# AnalogOut.net
KiCad netlist of a schematic drawn in Altium Designer
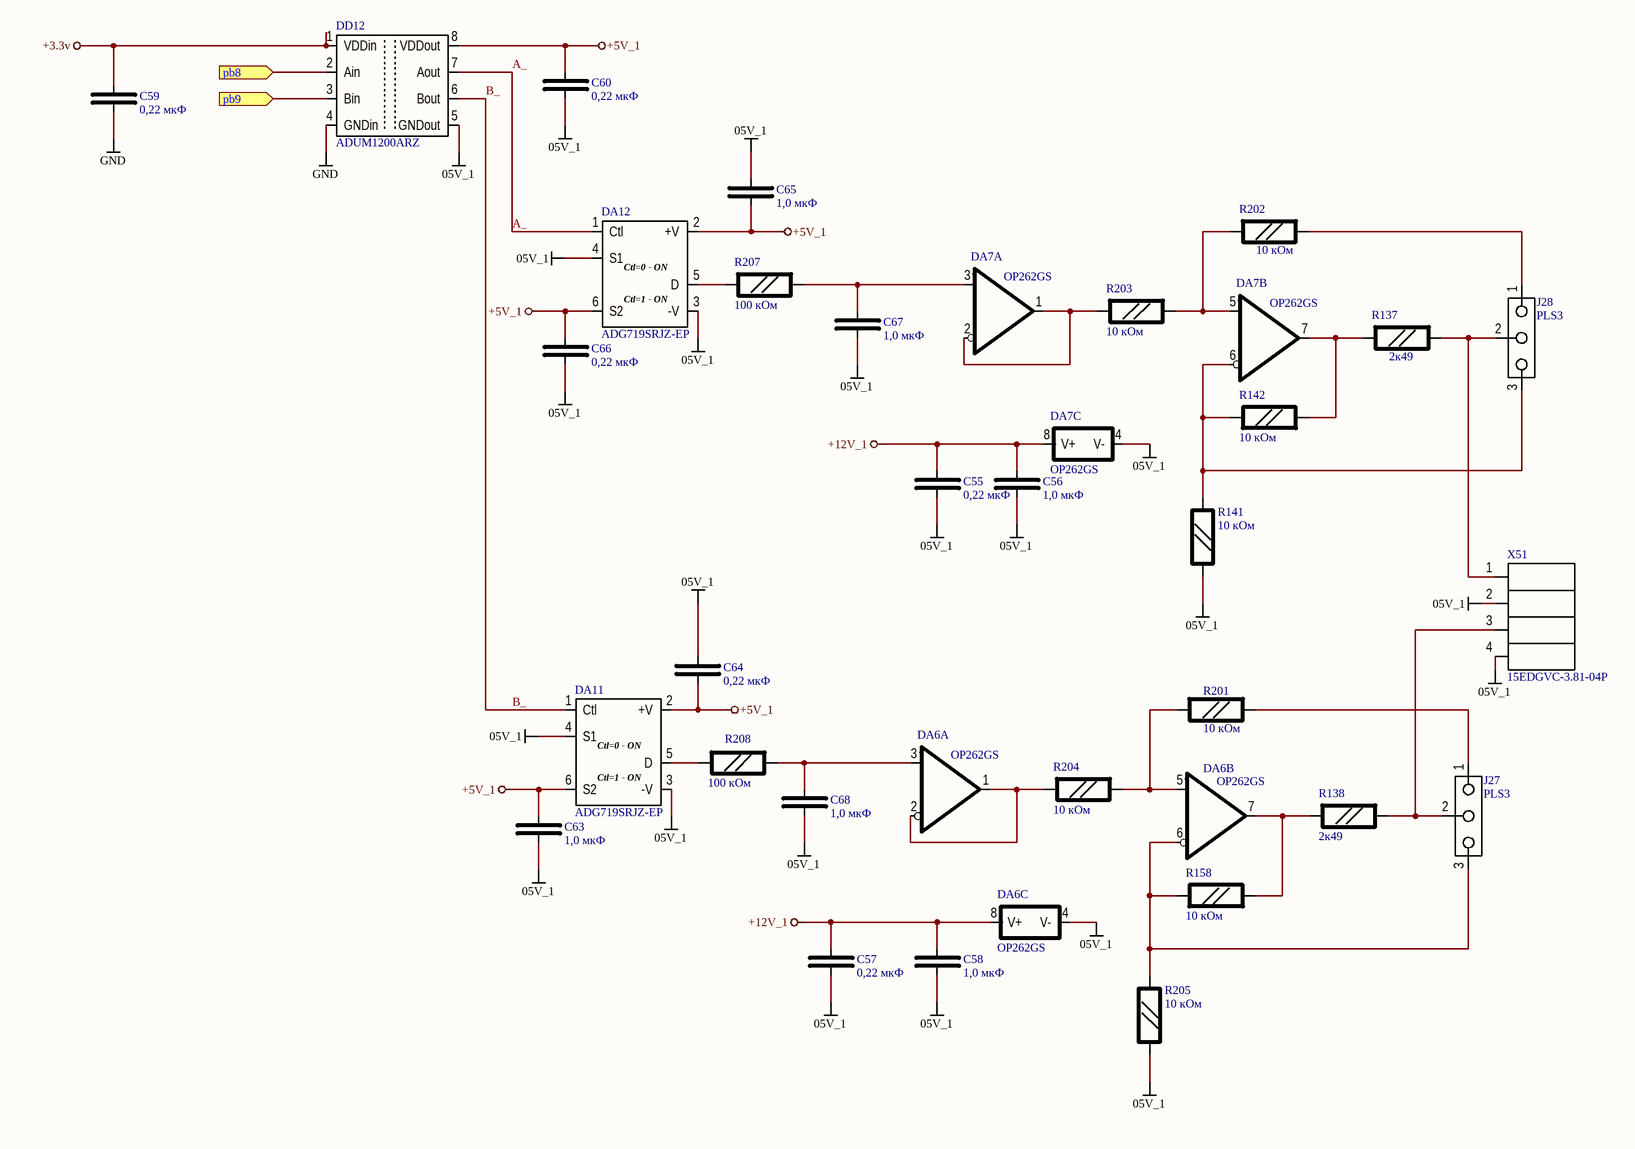
[diagram p0: AnalogOut.SchDoc]

(export (version "E")
  (design (tool "Eeschema 10.0.6"))
  (components
    (comp (ref "C55")
      (value "0,22 мкФ")
      (footprint "SMD0805CAP")
      (description "Чип конденсатор 0805")
      (fields (field (name "VOLTAGE") "50V"))
      (libsource (lib "SL02_22F") (part "C0805"))
    )
    (comp (ref "C56")
      (value "1,0 мкФ")
      (footprint "SMD0805CAP")
      (description "Чип конденсатор 0805")
      (fields (field (name "VOLTAGE") "50V"))
      (libsource (lib "SL02_22F") (part "C0805"))
    )
    (comp (ref "C57")
      (value "0,22 мкФ")
      (footprint "SMD0805CAP")
      (description "Чип конденсатор 0805")
      (fields (field (name "VOLTAGE") "50V"))
      (libsource (lib "SL02_22F") (part "C0805"))
    )
    (comp (ref "C58")
      (value "1,0 мкФ")
      (footprint "SMD0805CAP")
      (description "Чип конденсатор 0805")
      (fields (field (name "VOLTAGE") "50V"))
      (libsource (lib "SL02_22F") (part "C0805"))
    )
    (comp (ref "C59")
      (value "0,22 мкФ")
      (footprint "SMD0805CAP")
      (description "Чип конденсатор 0805")
      (fields (field (name "VOLTAGE") "50V"))
      (libsource (lib "SL02_22F") (part "C0805"))
    )
    (comp (ref "C60")
      (value "0,22 мкФ")
      (footprint "SMD0805CAP")
      (description "Чип конденсатор 0805")
      (fields (field (name "VOLTAGE") "50V"))
      (libsource (lib "SL02_22F") (part "C0805"))
    )
    (comp (ref "C63")
      (value "1,0 мкФ")
      (footprint "SMD0805CAP")
      (description "Чип конденсатор 0805")
      (fields (field (name "VOLTAGE") "50V"))
      (libsource (lib "SL02_22F") (part "C0805"))
    )
    (comp (ref "C64")
      (value "0,22 мкФ")
      (footprint "SMD0805CAP")
      (description "Чип конденсатор 0805")
      (fields (field (name "VOLTAGE") "50V"))
      (libsource (lib "SL02_22F") (part "C0805"))
    )
    (comp (ref "C65")
      (value "1,0 мкФ")
      (footprint "SMD0805CAP")
      (description "Чип конденсатор 0805")
      (fields (field (name "VOLTAGE") "50V"))
      (libsource (lib "SL02_22F") (part "C0805"))
    )
    (comp (ref "C66")
      (value "0,22 мкФ")
      (footprint "SMD0805CAP")
      (description "Чип конденсатор 0805")
      (fields (field (name "VOLTAGE") "50V"))
      (libsource (lib "SL02_22F") (part "C0805"))
    )
    (comp (ref "C67")
      (value "1,0 мкФ")
      (footprint "SMD0805CAP")
      (description "Чип конденсатор 0805")
      (fields (field (name "VOLTAGE") "50V"))
      (libsource (lib "SL02_22F") (part "C0805"))
    )
    (comp (ref "C68")
      (value "1,0 мкФ")
      (footprint "SMD0805CAP")
      (description "Чип конденсатор 0805")
      (fields (field (name "VOLTAGE") "50V"))
      (libsource (lib "SL02_22F") (part "C0805"))
    )
    (comp (ref "DA6")
      (value "OP262GS")
      (footprint "SO8")
      (description "ОУ сдвоенный R2R out")
      (fields (field (name "VOLTAGE") "2.7..12V"))
      (libsource (lib "SL02_22F") (part "OP262GS"))
    )
    (comp (ref "DA7")
      (value "OP262GS")
      (footprint "SO8")
      (description "ОУ сдвоенный R2R out")
      (fields (field (name "VOLTAGE") "2.7..12V"))
      (libsource (lib "SL02_22F") (part "OP262GS"))
    )
    (comp (ref "DA11")
      (value "ADG719SRJZ-EP")
      (footprint "SOT23-6")
      (description "аналоговый ключ SPDT")
      (fields (field (name "VOLTAGE") "1V8.. 5V5"))
      (libsource (lib "L02_22F") (part "ADG719BRJ"))
    )
    (comp (ref "DA12")
      (value "ADG719SRJZ-EP")
      (footprint "SOT23-6")
      (description "аналоговый ключ SPDT")
      (fields (field (name "VOLTAGE") "1V8.. 5V5"))
      (libsource (lib "L02_22F") (part "ADG719BRJ"))
    )
    (comp (ref "DD12")
      (value "ADUM1200ARZ")
      (footprint "SO8")
      (description "2х канальный цифровой изолятор")
      (fields (field (name "VOLTAGE") "3..5V"))
      (libsource (lib "L02_22F") (part "ADUM1200ARZ"))
    )
    (comp (ref "J27")
      (value "PLS3")
      (footprint "HDR1X3")
      (description "Джампер PLS3 2.54мм")
      (libsource (lib "L02_22F") (part "PLS3"))
    )
    (comp (ref "J28")
      (value "PLS3")
      (footprint "HDR1X3")
      (description "Джампер PLS3 2.54мм")
      (libsource (lib "L02_22F") (part "PLS3"))
    )
    (comp (ref "R137")
      (value "2к49")
      (footprint "SMD0805RES")
      (description "Чип резистор 0805")
      (fields (field (name "TOLERANCE") "1%"))
      (libsource (lib "SL02_22F") (part "R0805"))
    )
    (comp (ref "R138")
      (value "2к49")
      (footprint "SMD0805RES")
      (description "Чип резистор 0805")
      (fields (field (name "TOLERANCE") "1%"))
      (libsource (lib "SL02_22F") (part "R0805"))
    )
    (comp (ref "R141")
      (value "10 кОм")
      (footprint "SMD0805RES")
      (description "Чип резистор 0805")
      (fields (field (name "TOLERANCE") "1%"))
      (libsource (lib "SL02_22F") (part "R0805"))
    )
    (comp (ref "R142")
      (value "10 кОм")
      (footprint "SMD0805RES")
      (description "Чип резистор 0805")
      (fields (field (name "TOLERANCE") "1%"))
      (libsource (lib "SL02_22F") (part "R0805"))
    )
    (comp (ref "R158")
      (value "10 кОм")
      (footprint "SMD0805RES")
      (description "Чип резистор 0805")
      (fields (field (name "TOLERANCE") "1%"))
      (libsource (lib "SL02_22F") (part "R0805"))
    )
    (comp (ref "R201")
      (value "10 кОм")
      (footprint "SMD0805RES")
      (description "Чип резистор 0805")
      (fields (field (name "TOLERANCE") "1%"))
      (libsource (lib "SL02_22F") (part "R0805"))
    )
    (comp (ref "R202")
      (value "10 кОм")
      (footprint "SMD0805RES")
      (description "Чип резистор 0805")
      (fields (field (name "TOLERANCE") "1%"))
      (libsource (lib "SL02_22F") (part "R0805"))
    )
    (comp (ref "R203")
      (value "10 кОм")
      (footprint "SMD0805RES")
      (description "Чип резистор 0805")
      (fields (field (name "TOLERANCE") "1%"))
      (libsource (lib "SL02_22F") (part "R0805"))
    )
    (comp (ref "R204")
      (value "10 кОм")
      (footprint "SMD0805RES")
      (description "Чип резистор 0805")
      (fields (field (name "TOLERANCE") "1%"))
      (libsource (lib "SL02_22F") (part "R0805"))
    )
    (comp (ref "R205")
      (value "10 кОм")
      (footprint "SMD0805RES")
      (description "Чип резистор 0805")
      (fields (field (name "TOLERANCE") "1%"))
      (libsource (lib "SL02_22F") (part "R0805"))
    )
    (comp (ref "R207")
      (value "100 кОм")
      (footprint "SMD0805RES")
      (description "Чип резистор 0805")
      (fields (field (name "TOLERANCE") "5%"))
      (libsource (lib "SL02_22F") (part "R0805"))
    )
    (comp (ref "R208")
      (value "100 кОм")
      (footprint "SMD0805RES")
      (description "Чип резистор 0805")
      (fields (field (name "TOLERANCE") "5%"))
      (libsource (lib "SL02_22F") (part "R0805"))
    )
    (comp (ref "X51")
      (value "15EDGVC-3.81-04P")
      (footprint "15EDGVC_081_4")
      (description "Вилка  4/3.81")
      (fields (field (name "VOLTAGE") "2кВ"))
      (libsource (lib "L02_22F") (part "15EDGVC-3.81-04P"))
    )
  )
  (nets
    (net (code "1") (name "+3.3v") (class "Default")
      (node (ref "C59") (pin "1") (pinfunction "1_1") (pintype "passive"))
      (node (ref "DD12") (pin "1") (pinfunction "VDDin_1") (pintype "power_in"))
    )
    (net (code "2") (name "+5V_1") (class "Default")
      (node (ref "C60") (pin "1") (pinfunction "1_1") (pintype "passive"))
      (node (ref "C63") (pin "1") (pinfunction "1_1") (pintype "passive"))
      (node (ref "C64") (pin "1") (pinfunction "1_1") (pintype "passive"))
      (node (ref "C65") (pin "1") (pinfunction "1_1") (pintype "passive"))
      (node (ref "C66") (pin "1") (pinfunction "1_1") (pintype "passive"))
      (node (ref "DA11") (pin "2") (pinfunction "+V_2") (pintype "power_in"))
      (node (ref "DA11") (pin "6") (pinfunction "S2_6") (pintype "passive"))
      (node (ref "DA12") (pin "2") (pinfunction "+V_2") (pintype "power_in"))
      (node (ref "DA12") (pin "6") (pinfunction "S2_6") (pintype "passive"))
      (node (ref "DD12") (pin "8") (pinfunction "VDDout_8") (pintype "power_in"))
    )
    (net (code "3") (name "+12V_1") (class "Default")
      (node (ref "C55") (pin "1") (pinfunction "1_1") (pintype "passive"))
      (node (ref "C56") (pin "1") (pinfunction "1_1") (pintype "passive"))
      (node (ref "C57") (pin "1") (pinfunction "1_1") (pintype "passive"))
      (node (ref "C58") (pin "1") (pinfunction "1_1") (pintype "passive"))
      (node (ref "DA6") (pin "8") (pinfunction "V+_8") (pintype "power_in"))
      (node (ref "DA7") (pin "8") (pinfunction "V+_8") (pintype "power_in"))
    )
    (net (code "4") (name "/A_") (class "Default")
      (node (ref "DA12") (pin "1") (pinfunction "Ctl_1") (pintype "input"))
      (node (ref "DD12") (pin "7") (pinfunction "Aout_7") (pintype "output"))
    )
    (net (code "5") (name "/B_") (class "Default")
      (node (ref "DA11") (pin "1") (pinfunction "Ctl_1") (pintype "input"))
      (node (ref "DD12") (pin "6") (pinfunction "Bout_6") (pintype "output"))
    )
    (net (code "6") (name "/pb8") (class "Default")
      (node (ref "DD12") (pin "2") (pinfunction "Ain_2") (pintype "input"))
    )
    (net (code "7") (name "/pb9") (class "Default")
      (node (ref "DD12") (pin "3") (pinfunction "Bin_3") (pintype "input"))
    )
    (net (code "8") (name "05V_1") (class "Default")
      (node (ref "C55") (pin "2") (pinfunction "2_2") (pintype "passive"))
      (node (ref "C56") (pin "2") (pinfunction "2_2") (pintype "passive"))
      (node (ref "C57") (pin "2") (pinfunction "2_2") (pintype "passive"))
      (node (ref "C58") (pin "2") (pinfunction "2_2") (pintype "passive"))
      (node (ref "C60") (pin "2") (pinfunction "2_2") (pintype "passive"))
      (node (ref "C63") (pin "2") (pinfunction "2_2") (pintype "passive"))
      (node (ref "C64") (pin "2") (pinfunction "2_2") (pintype "passive"))
      (node (ref "C65") (pin "2") (pinfunction "2_2") (pintype "passive"))
      (node (ref "C66") (pin "2") (pinfunction "2_2") (pintype "passive"))
      (node (ref "C67") (pin "2") (pinfunction "2_2") (pintype "passive"))
      (node (ref "C68") (pin "2") (pinfunction "2_2") (pintype "passive"))
      (node (ref "DA11") (pin "3") (pinfunction "-V_3") (pintype "power_in"))
      (node (ref "DA11") (pin "4") (pinfunction "S1_4") (pintype "passive"))
      (node (ref "DA12") (pin "3") (pinfunction "-V_3") (pintype "power_in"))
      (node (ref "DA12") (pin "4") (pinfunction "S1_4") (pintype "passive"))
      (node (ref "DA6") (pin "4") (pinfunction "V-_4") (pintype "power_in"))
      (node (ref "DA7") (pin "4") (pinfunction "V-_4") (pintype "power_in"))
      (node (ref "DD12") (pin "5") (pinfunction "GNDout_5") (pintype "power_in"))
      (node (ref "R141") (pin "1") (pinfunction "1_1") (pintype "passive"))
      (node (ref "R205") (pin "1") (pinfunction "1_1") (pintype "passive"))
      (node (ref "X51") (pin "2") (pinfunction "2_2") (pintype "passive"))
      (node (ref "X51") (pin "4") (pinfunction "4_4") (pintype "passive"))
    )
    (net (code "9") (name "GND") (class "Default")
      (node (ref "C59") (pin "2") (pinfunction "2_2") (pintype "passive"))
      (node (ref "DD12") (pin "4") (pinfunction "GNDin_4") (pintype "power_in"))
    )
    (net (code "10") (name "Net-(DA6A-+)") (class "Default")
      (node (ref "C68") (pin "1") (pinfunction "1_1") (pintype "passive"))
      (node (ref "DA6") (pin "3") (pinfunction "+_3") (pintype "input"))
      (node (ref "R208") (pin "2") (pinfunction "2_2") (pintype "passive"))
    )
    (net (code "11") (name "Net-(DA6A--)") (class "Default")
      (node (ref "DA6") (pin "1") (pinfunction "OUT_1") (pintype "output"))
      (node (ref "DA6") (pin "2") (pinfunction "-_2") (pintype "input"))
      (node (ref "R204") (pin "1") (pinfunction "1_1") (pintype "passive"))
    )
    (net (code "12") (name "Net-(DA6B-+)") (class "Default")
      (node (ref "DA6") (pin "5") (pinfunction "+_5") (pintype "input"))
      (node (ref "R201") (pin "1") (pinfunction "1_1") (pintype "passive"))
      (node (ref "R204") (pin "2") (pinfunction "2_2") (pintype "passive"))
    )
    (net (code "13") (name "Net-(DA6B--)") (class "Default")
      (node (ref "DA6") (pin "6") (pinfunction "-_6") (pintype "passive"))
      (node (ref "J27") (pin "3") (pinfunction "Left_3") (pintype "passive"))
      (node (ref "R158") (pin "2") (pinfunction "2_2") (pintype "passive"))
      (node (ref "R205") (pin "2") (pinfunction "2_2") (pintype "passive"))
    )
    (net (code "14") (name "Net-(DA6B-OUT)") (class "Default")
      (node (ref "DA6") (pin "7") (pinfunction "OUT_7") (pintype "passive"))
      (node (ref "R138") (pin "1") (pinfunction "1_1") (pintype "passive"))
      (node (ref "R158") (pin "1") (pinfunction "1_1") (pintype "passive"))
    )
    (net (code "15") (name "Net-(DA7A-+)") (class "Default")
      (node (ref "C67") (pin "1") (pinfunction "1_1") (pintype "passive"))
      (node (ref "DA7") (pin "3") (pinfunction "+_3") (pintype "input"))
      (node (ref "R207") (pin "2") (pinfunction "2_2") (pintype "passive"))
    )
    (net (code "16") (name "Net-(DA7A--)") (class "Default")
      (node (ref "DA7") (pin "1") (pinfunction "OUT_1") (pintype "output"))
      (node (ref "DA7") (pin "2") (pinfunction "-_2") (pintype "input"))
      (node (ref "R203") (pin "1") (pinfunction "1_1") (pintype "passive"))
    )
    (net (code "17") (name "Net-(DA7B-+)") (class "Default")
      (node (ref "DA7") (pin "5") (pinfunction "+_5") (pintype "input"))
      (node (ref "R202") (pin "1") (pinfunction "1_1") (pintype "passive"))
      (node (ref "R203") (pin "2") (pinfunction "2_2") (pintype "passive"))
    )
    (net (code "18") (name "Net-(DA7B--)") (class "Default")
      (node (ref "DA7") (pin "6") (pinfunction "-_6") (pintype "passive"))
      (node (ref "J28") (pin "3") (pinfunction "Left_3") (pintype "passive"))
      (node (ref "R141") (pin "2") (pinfunction "2_2") (pintype "passive"))
      (node (ref "R142") (pin "2") (pinfunction "2_2") (pintype "passive"))
    )
    (net (code "19") (name "Net-(DA7B-OUT)") (class "Default")
      (node (ref "DA7") (pin "7") (pinfunction "OUT_7") (pintype "passive"))
      (node (ref "R137") (pin "1") (pinfunction "1_1") (pintype "passive"))
      (node (ref "R142") (pin "1") (pinfunction "1_1") (pintype "passive"))
    )
    (net (code "20") (name "Net-(DA11-D)") (class "Default")
      (node (ref "DA11") (pin "5") (pinfunction "D_5") (pintype "power_in"))
      (node (ref "R208") (pin "1") (pinfunction "1_1") (pintype "passive"))
    )
    (net (code "21") (name "Net-(DA12-D)") (class "Default")
      (node (ref "DA12") (pin "5") (pinfunction "D_5") (pintype "power_in"))
      (node (ref "R207") (pin "1") (pinfunction "1_1") (pintype "passive"))
    )
    (net (code "22") (name "Net-(J27-Cetnter)") (class "Default")
      (node (ref "J27") (pin "2") (pinfunction "Cetnter_2") (pintype "passive"))
      (node (ref "R138") (pin "2") (pinfunction "2_2") (pintype "passive"))
      (node (ref "X51") (pin "3") (pinfunction "3_3") (pintype "passive"))
    )
    (net (code "23") (name "Net-(J27-Right)") (class "Default")
      (node (ref "J27") (pin "1") (pinfunction "Right_1") (pintype "passive"))
      (node (ref "R201") (pin "2") (pinfunction "2_2") (pintype "passive"))
    )
    (net (code "24") (name "Net-(J28-Cetnter)") (class "Default")
      (node (ref "J28") (pin "2") (pinfunction "Cetnter_2") (pintype "passive"))
      (node (ref "R137") (pin "2") (pinfunction "2_2") (pintype "passive"))
      (node (ref "X51") (pin "1") (pinfunction "1_1") (pintype "passive"))
    )
    (net (code "25") (name "Net-(J28-Right)") (class "Default")
      (node (ref "J28") (pin "1") (pinfunction "Right_1") (pintype "passive"))
      (node (ref "R202") (pin "2") (pinfunction "2_2") (pintype "passive"))
    )
  )
)
